# openSX70-dongle_SEEED_v400.net
KiCad netlist of a schematic drawn in EAGLE
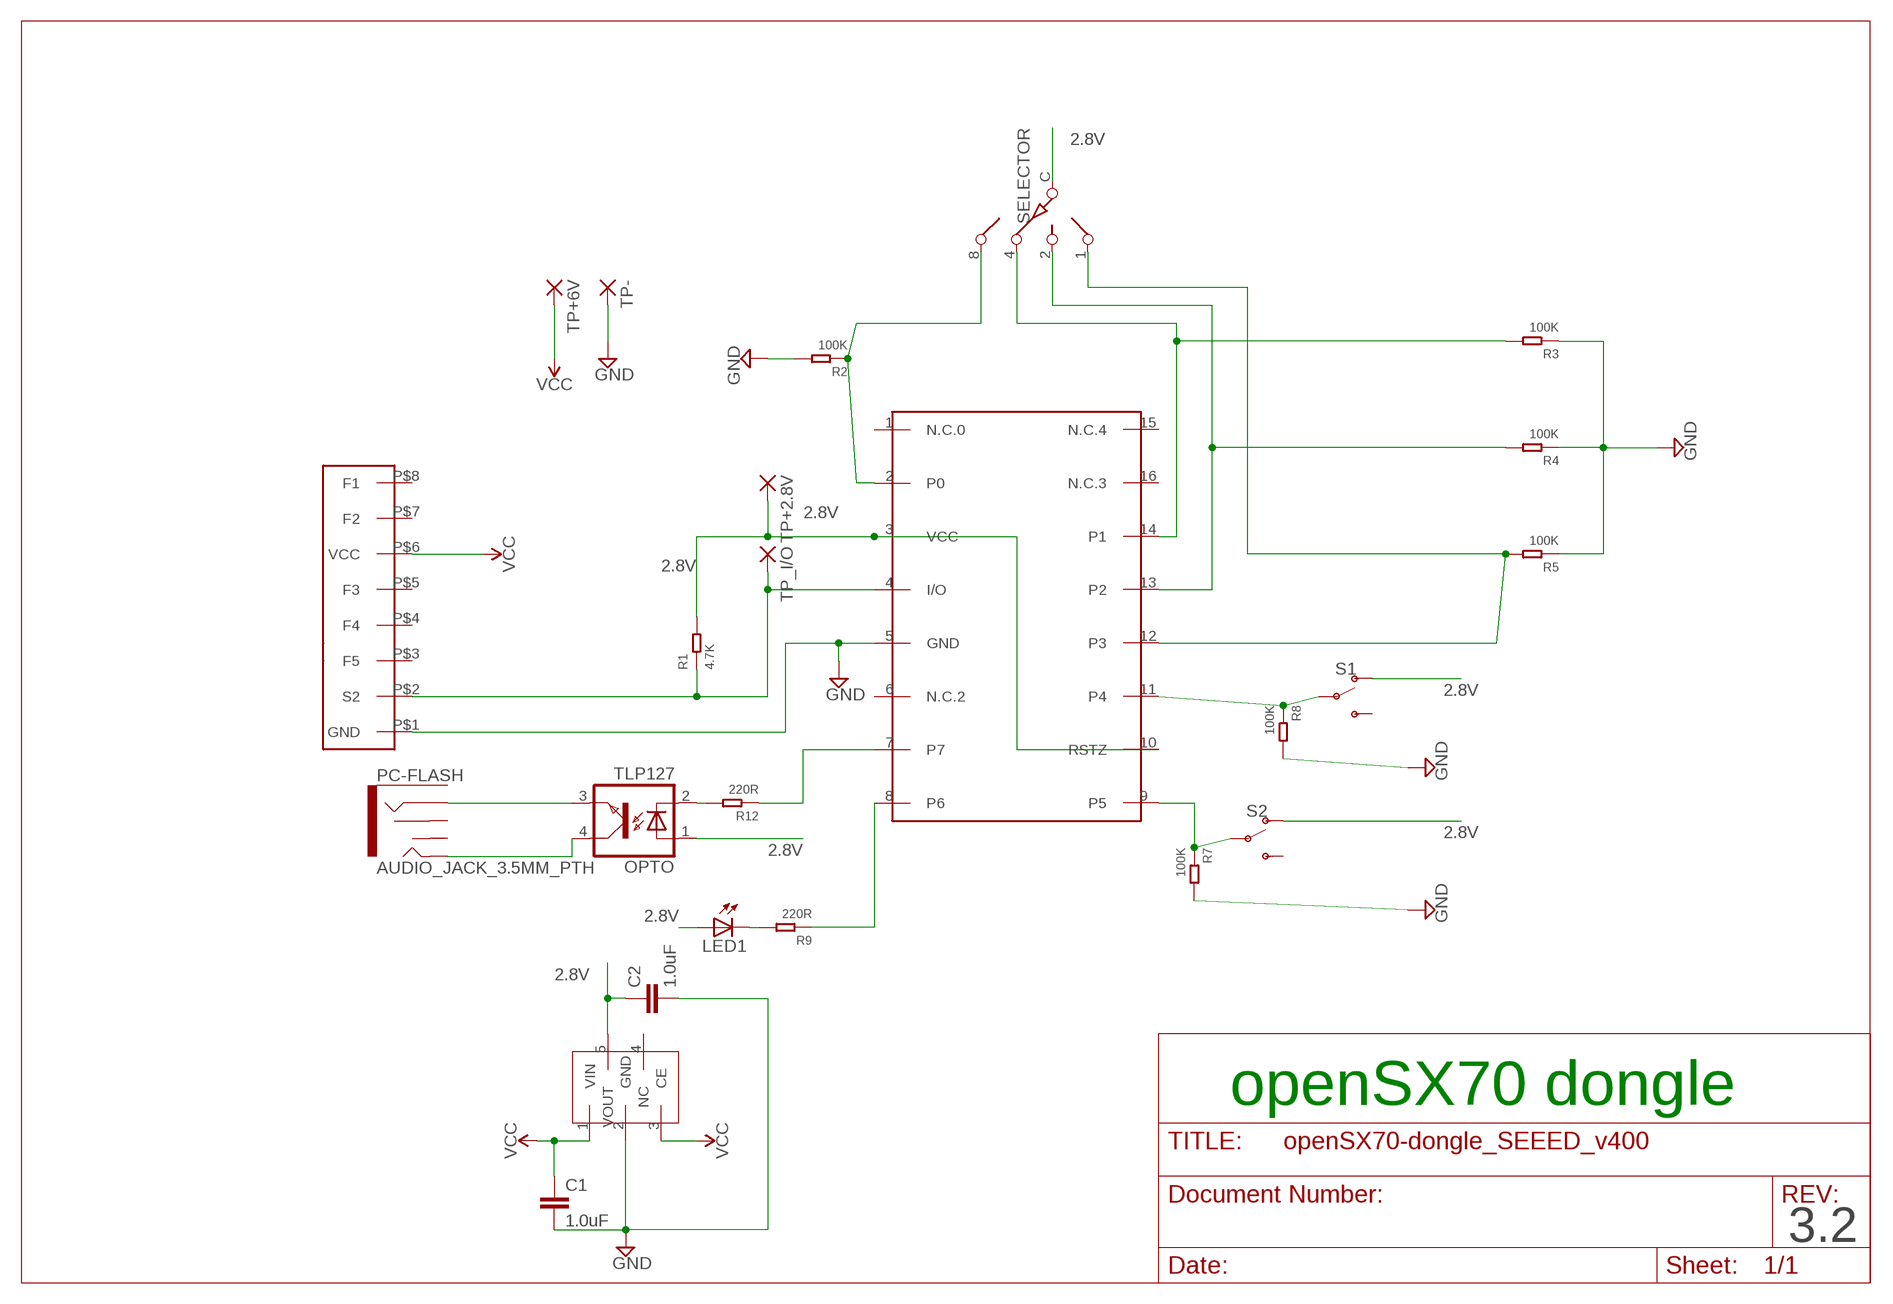
[diagram p0: schematic, sheet 1]

(export (version "E")
  (design (tool "Eeschema 10.0.6"))
  (components
    (comp (ref "C1")
      (value "1.0uF")
      (footprint "eagle-import:C0603")
      (libsource (lib "eagle-import") (part "C-EUC0603"))
    )
    (comp (ref "C2")
      (value "1.0uF")
      (footprint "eagle-import:C0603")
      (libsource (lib "eagle-import") (part "C-EUC0603"))
    )
    (comp (ref "DS2408")
      (value "DS2408")
      (footprint "eagle-import:SO16")
      (libsource (lib "eagle-import") (part "DS2408"))
    )
    (comp (ref "LED1")
      (value "LED3MM")
      (footprint "eagle-import:LED3MM")
      (libsource (lib "eagle-import") (part "LED3MM"))
    )
    (comp (ref "OPTO")
      (value "TLP127")
      (footprint "eagle-import:SO-4")
      (libsource (lib "eagle-import") (part "TLP127"))
    )
    (comp (ref "PC-FLASH")
      (value "AUDIO_JACK_3.5MM_PTH")
      (footprint "eagle-import:AUDIO-JACK")
      (libsource (lib "eagle-import") (part "AUDIO_JACK_3.5MM_PTH"))
    )
    (comp (ref "R1")
      (value "4.7K")
      (footprint "eagle-import:R0603")
      (fields (field (name "MPN") "RC0603JR-074K7L"))
      (libsource (lib "eagle-import") (part "SMD-RES-4.7K-5%-1/10W(0603)"))
    )
    (comp (ref "R2")
      (value "100K")
      (footprint "eagle-import:R0603")
      (fields (field (name "MPN") "RC0603FR-07100KL"))
      (libsource (lib "eagle-import") (part "SMD-RES-100K-1%-1/10W(0603)"))
    )
    (comp (ref "R3")
      (value "100K")
      (footprint "eagle-import:R0603")
      (fields (field (name "MPN") "RC0603FR-07100KL"))
      (libsource (lib "eagle-import") (part "SMD-RES-100K-1%-1/10W(0603)"))
    )
    (comp (ref "R4")
      (value "100K")
      (footprint "eagle-import:R0603")
      (fields (field (name "MPN") "RC0603FR-07100KL"))
      (libsource (lib "eagle-import") (part "SMD-RES-100K-1%-1/10W(0603)"))
    )
    (comp (ref "R5")
      (value "100K")
      (footprint "eagle-import:R0603")
      (fields (field (name "MPN") "RC0603FR-07100KL"))
      (libsource (lib "eagle-import") (part "SMD-RES-100K-1%-1/10W(0603)"))
    )
    (comp (ref "R7")
      (value "100K")
      (footprint "eagle-import:R0603")
      (fields (field (name "MPN") "RC0603FR-07100KL"))
      (libsource (lib "eagle-import") (part "SMD-RES-100K-1%-1/10W(0603)"))
    )
    (comp (ref "R8")
      (value "100K")
      (footprint "eagle-import:R0603")
      (fields (field (name "MPN") "RC0603FR-07100KL"))
      (libsource (lib "eagle-import") (part "SMD-RES-100K-1%-1/10W(0603)"))
    )
    (comp (ref "R9")
      (value "220R")
      (footprint "eagle-import:R0603")
      (fields (field (name "MPN") "RC0603JR-07220RL"))
      (libsource (lib "eagle-import") (part "SMD-RES-220R-5%-1/10W(0603)"))
    )
    (comp (ref "R12")
      (value "220R")
      (footprint "eagle-import:R0603")
      (fields (field (name "MPN") "RC0603JR-07220RL"))
      (libsource (lib "eagle-import") (part "SMD-RES-220R-5%-1/10W(0603)"))
    )
    (comp (ref "REG")
      (value "NCP4688")
      (footprint "eagle-import:SOT-23-5")
      (libsource (lib "eagle-import") (part "NCP4688"))
    )
    (comp (ref "S1")
      (value "SWITCH-SPDT-SMD-RIGHT-ANGLE")
      (footprint "eagle-import:SWITCH_SPST_SMD_A")
      (libsource (lib "eagle-import") (part "SWITCH-SPDT-SMD-RIGHT-ANGLE"))
    )
    (comp (ref "S2")
      (value "SWITCH-SPDT-SMD-RIGHT-ANGLE")
      (footprint "eagle-import:SWITCH_SPST_SMD_A")
      (libsource (lib "eagle-import") (part "SWITCH-SPDT-SMD-RIGHT-ANGLE"))
    )
    (comp (ref "SELECTOR")
      (value "SW-C16")
      (footprint "eagle-import:SW-C16")
      (libsource (lib "eagle-import") (part "SW-C16"))
    )
    (comp (ref "TP+2.8V")
      (value "SMD2")
      (footprint "eagle-import:SMD1,27-2,54")
      (libsource (lib "eagle-import") (part "SMD2"))
    )
    (comp (ref "TP+6V")
      (value "SMD2")
      (footprint "eagle-import:SMD1,27-2,54")
      (libsource (lib "eagle-import") (part "SMD2"))
    )
    (comp (ref "TP-")
      (value "SMD2")
      (footprint "eagle-import:SMD1,27-2,54")
      (libsource (lib "eagle-import") (part "SMD2"))
    )
    (comp (ref "TP_I/O")
      (value "SMD2")
      (footprint "eagle-import:SMD1,27-2,54")
      (libsource (lib "eagle-import") (part "SMD2"))
    )
    (comp (ref "U$1")
      (value "FLASH-EDGE-CONNECTOR")
      (footprint "eagle-import:FLASH-EDGE-8")
      (libsource (lib "eagle-import") (part "FLASH-EDGE-CONNECTOR"))
    )
  )
  (nets
    (net (code "1") (name "/2.8V") (class "Default")
      (node (ref "C2") (pin "1") (pinfunction "1_1") (pintype "passive"))
      (node (ref "DS2408") (pin "10") (pinfunction "RSTZ_10") (pintype "bidirectional"))
      (node (ref "DS2408") (pin "3") (pinfunction "VCC_3") (pintype "bidirectional"))
      (node (ref "LED1") (pin "A") (pinfunction "A_A") (pintype "passive"))
      (node (ref "OPTO") (pin "1") (pinfunction "A_1") (pintype "passive"))
      (node (ref "R1") (pin "2") (pinfunction "2_2") (pintype "passive"))
      (node (ref "REG") (pin "5") (pinfunction "VOUT_5") (pintype "bidirectional"))
      (node (ref "S1") (pin "1") (pinfunction "O_1") (pintype "passive"))
      (node (ref "S2") (pin "1") (pinfunction "O_1") (pintype "passive"))
      (node (ref "SELECTOR") (pin "C") (pinfunction "C_C") (pintype "passive"))
      (node (ref "TP+2.8V") (pin "1") (pinfunction "P_1") (pintype "passive"))
    )
    (net (code "2") (name "GND") (class "Default")
      (node (ref "C1") (pin "2") (pinfunction "2_2") (pintype "passive"))
      (node (ref "C2") (pin "2") (pinfunction "2_2") (pintype "passive"))
      (node (ref "DS2408") (pin "5") (pinfunction "GND_5") (pintype "bidirectional"))
      (node (ref "R2") (pin "2") (pinfunction "2_2") (pintype "passive"))
      (node (ref "R3") (pin "1") (pinfunction "1_1") (pintype "passive"))
      (node (ref "R4") (pin "1") (pinfunction "1_1") (pintype "passive"))
      (node (ref "R5") (pin "1") (pinfunction "1_1") (pintype "passive"))
      (node (ref "R7") (pin "2") (pinfunction "2_2") (pintype "passive"))
      (node (ref "R8") (pin "2") (pinfunction "2_2") (pintype "passive"))
      (node (ref "REG") (pin "2") (pinfunction "GND_2") (pintype "bidirectional"))
      (node (ref "TP-") (pin "1") (pinfunction "P_1") (pintype "passive"))
      (node (ref "U$1") (pin "P$1") (pinfunction "GND_P$1") (pintype "bidirectional"))
    )
    (net (code "3") (name "Net-(DS2408-I{slash}O)") (class "Default")
      (node (ref "DS2408") (pin "4") (pinfunction "I/O_4") (pintype "bidirectional"))
      (node (ref "R1") (pin "1") (pinfunction "1_1") (pintype "passive"))
      (node (ref "TP_I/O") (pin "1") (pinfunction "P_1") (pintype "passive"))
      (node (ref "U$1") (pin "P$2") (pinfunction "S2_P$2") (pintype "bidirectional"))
    )
    (net (code "4") (name "Net-(DS2408-P0)") (class "Default")
      (node (ref "DS2408") (pin "2") (pinfunction "P0_2") (pintype "bidirectional"))
      (node (ref "R2") (pin "1") (pinfunction "1_1") (pintype "passive"))
      (node (ref "SELECTOR") (pin "8") (pinfunction "8_8") (pintype "passive"))
    )
    (net (code "5") (name "Net-(DS2408-P1)") (class "Default")
      (node (ref "DS2408") (pin "14") (pinfunction "P1_14") (pintype "bidirectional"))
      (node (ref "R3") (pin "2") (pinfunction "2_2") (pintype "passive"))
      (node (ref "SELECTOR") (pin "4") (pinfunction "4_4") (pintype "passive"))
    )
    (net (code "6") (name "Net-(DS2408-P2)") (class "Default")
      (node (ref "DS2408") (pin "13") (pinfunction "P2_13") (pintype "bidirectional"))
      (node (ref "R4") (pin "2") (pinfunction "2_2") (pintype "passive"))
      (node (ref "SELECTOR") (pin "2") (pinfunction "2_2") (pintype "passive"))
    )
    (net (code "7") (name "Net-(DS2408-P3)") (class "Default")
      (node (ref "DS2408") (pin "12") (pinfunction "P3_12") (pintype "bidirectional"))
      (node (ref "R5") (pin "2") (pinfunction "2_2") (pintype "passive"))
      (node (ref "SELECTOR") (pin "1") (pinfunction "1_1") (pintype "passive"))
    )
    (net (code "8") (name "Net-(DS2408-P4)") (class "Default")
      (node (ref "DS2408") (pin "11") (pinfunction "P4_11") (pintype "bidirectional"))
      (node (ref "R8") (pin "1") (pinfunction "1_1") (pintype "passive"))
      (node (ref "S1") (pin "2") (pinfunction "P_2") (pintype "passive"))
    )
    (net (code "9") (name "Net-(DS2408-P5)") (class "Default")
      (node (ref "DS2408") (pin "9") (pinfunction "P5_9") (pintype "bidirectional"))
      (node (ref "R7") (pin "1") (pinfunction "1_1") (pintype "passive"))
      (node (ref "S2") (pin "2") (pinfunction "P_2") (pintype "passive"))
    )
    (net (code "10") (name "Net-(DS2408-P6)") (class "Default")
      (node (ref "DS2408") (pin "8") (pinfunction "P6_8") (pintype "bidirectional"))
      (node (ref "R9") (pin "1") (pinfunction "1_1") (pintype "passive"))
    )
    (net (code "11") (name "Net-(DS2408-P7)") (class "Default")
      (node (ref "DS2408") (pin "7") (pinfunction "P7_7") (pintype "bidirectional"))
      (node (ref "R12") (pin "1") (pinfunction "1_1") (pintype "passive"))
    )
    (net (code "12") (name "Net-(LED1-C)") (class "Default")
      (node (ref "LED1") (pin "K") (pinfunction "C_K") (pintype "passive"))
      (node (ref "R9") (pin "2") (pinfunction "2_2") (pintype "passive"))
    )
    (net (code "13") (name "Net-(OPTO-C)") (class "Default")
      (node (ref "OPTO") (pin "2") (pinfunction "C_2") (pintype "passive"))
      (node (ref "R12") (pin "2") (pinfunction "2_2") (pintype "passive"))
    )
    (net (code "14") (name "Net-(OPTO-COL)") (class "Default")
      (node (ref "OPTO") (pin "4") (pinfunction "COL_4") (pintype "passive"))
      (node (ref "PC-FLASH") (pin "TIP") (pinfunction "TIP_TIP") (pintype "bidirectional"))
    )
    (net (code "15") (name "Net-(OPTO-EMIT)") (class "Default")
      (node (ref "OPTO") (pin "3") (pinfunction "EMIT_3") (pintype "passive"))
      (node (ref "PC-FLASH") (pin "RING") (pinfunction "RING_RING") (pintype "bidirectional"))
    )
    (net (code "16") (name "VCC") (class "Default")
      (node (ref "C1") (pin "1") (pinfunction "1_1") (pintype "passive"))
      (node (ref "REG") (pin "1") (pinfunction "VIN_1") (pintype "bidirectional"))
      (node (ref "REG") (pin "3") (pinfunction "CE_3") (pintype "bidirectional"))
      (node (ref "TP+6V") (pin "1") (pinfunction "P_1") (pintype "passive"))
      (node (ref "U$1") (pin "P$6") (pinfunction "VCC_P$6") (pintype "bidirectional"))
    )
    (net (code "17") (name "unconnected-(DS2408-N.C.0-Pad1)") (class "Default")
      (node (ref "DS2408") (pin "1") (pinfunction "N.C.0_1") (pintype "bidirectional"))
    )
    (net (code "18") (name "unconnected-(DS2408-N.C.2-Pad6)") (class "Default")
      (node (ref "DS2408") (pin "6") (pinfunction "N.C.2_6") (pintype "bidirectional"))
    )
    (net (code "19") (name "unconnected-(DS2408-N.C.3-Pad16)") (class "Default")
      (node (ref "DS2408") (pin "16") (pinfunction "N.C.3_16") (pintype "bidirectional"))
    )
    (net (code "20") (name "unconnected-(DS2408-N.C.4-Pad15)") (class "Default")
      (node (ref "DS2408") (pin "15") (pinfunction "N.C.4_15") (pintype "bidirectional"))
    )
    (net (code "21") (name "unconnected-(PC-FLASH-PadRSH)") (class "Default")
      (node (ref "PC-FLASH") (pin "RSH") (pinfunction "RSH_RSH") (pintype "bidirectional"))
    )
    (net (code "22") (name "unconnected-(PC-FLASH-PadSLEEVE)") (class "Default")
      (node (ref "PC-FLASH") (pin "SLEEVE") (pinfunction "SLEEVE_SLEEVE") (pintype "bidirectional"))
    )
    (net (code "23") (name "unconnected-(PC-FLASH-PadTSH)") (class "Default")
      (node (ref "PC-FLASH") (pin "TSH") (pinfunction "TSH_TSH") (pintype "bidirectional"))
    )
    (net (code "24") (name "unconnected-(REG-NC-Pad4)") (class "Default")
      (node (ref "REG") (pin "4") (pinfunction "NC_4") (pintype "bidirectional"))
    )
    (net (code "25") (name "unconnected-(S1-S-Pad3)") (class "Default")
      (node (ref "S1") (pin "3") (pinfunction "S_3") (pintype "passive"))
    )
    (net (code "26") (name "unconnected-(S2-S-Pad3)") (class "Default")
      (node (ref "S2") (pin "3") (pinfunction "S_3") (pintype "passive"))
    )
    (net (code "27") (name "unconnected-(U$1-F1-PadP$8)") (class "Default")
      (node (ref "U$1") (pin "P$8") (pinfunction "F1_P$8") (pintype "bidirectional"))
    )
    (net (code "28") (name "unconnected-(U$1-F2-PadP$7)") (class "Default")
      (node (ref "U$1") (pin "P$7") (pinfunction "F2_P$7") (pintype "bidirectional"))
    )
    (net (code "29") (name "unconnected-(U$1-F3-PadP$5)") (class "Default")
      (node (ref "U$1") (pin "P$5") (pinfunction "F3_P$5") (pintype "bidirectional"))
    )
    (net (code "30") (name "unconnected-(U$1-F4-PadP$4)") (class "Default")
      (node (ref "U$1") (pin "P$4") (pinfunction "F4_P$4") (pintype "bidirectional"))
    )
    (net (code "31") (name "unconnected-(U$1-F5-PadP$3)") (class "Default")
      (node (ref "U$1") (pin "P$3") (pinfunction "F5_P$3") (pintype "bidirectional"))
    )
  )
)
